# PCB_LTC6752.net
KiCad netlist of a schematic drawn in EAGLE
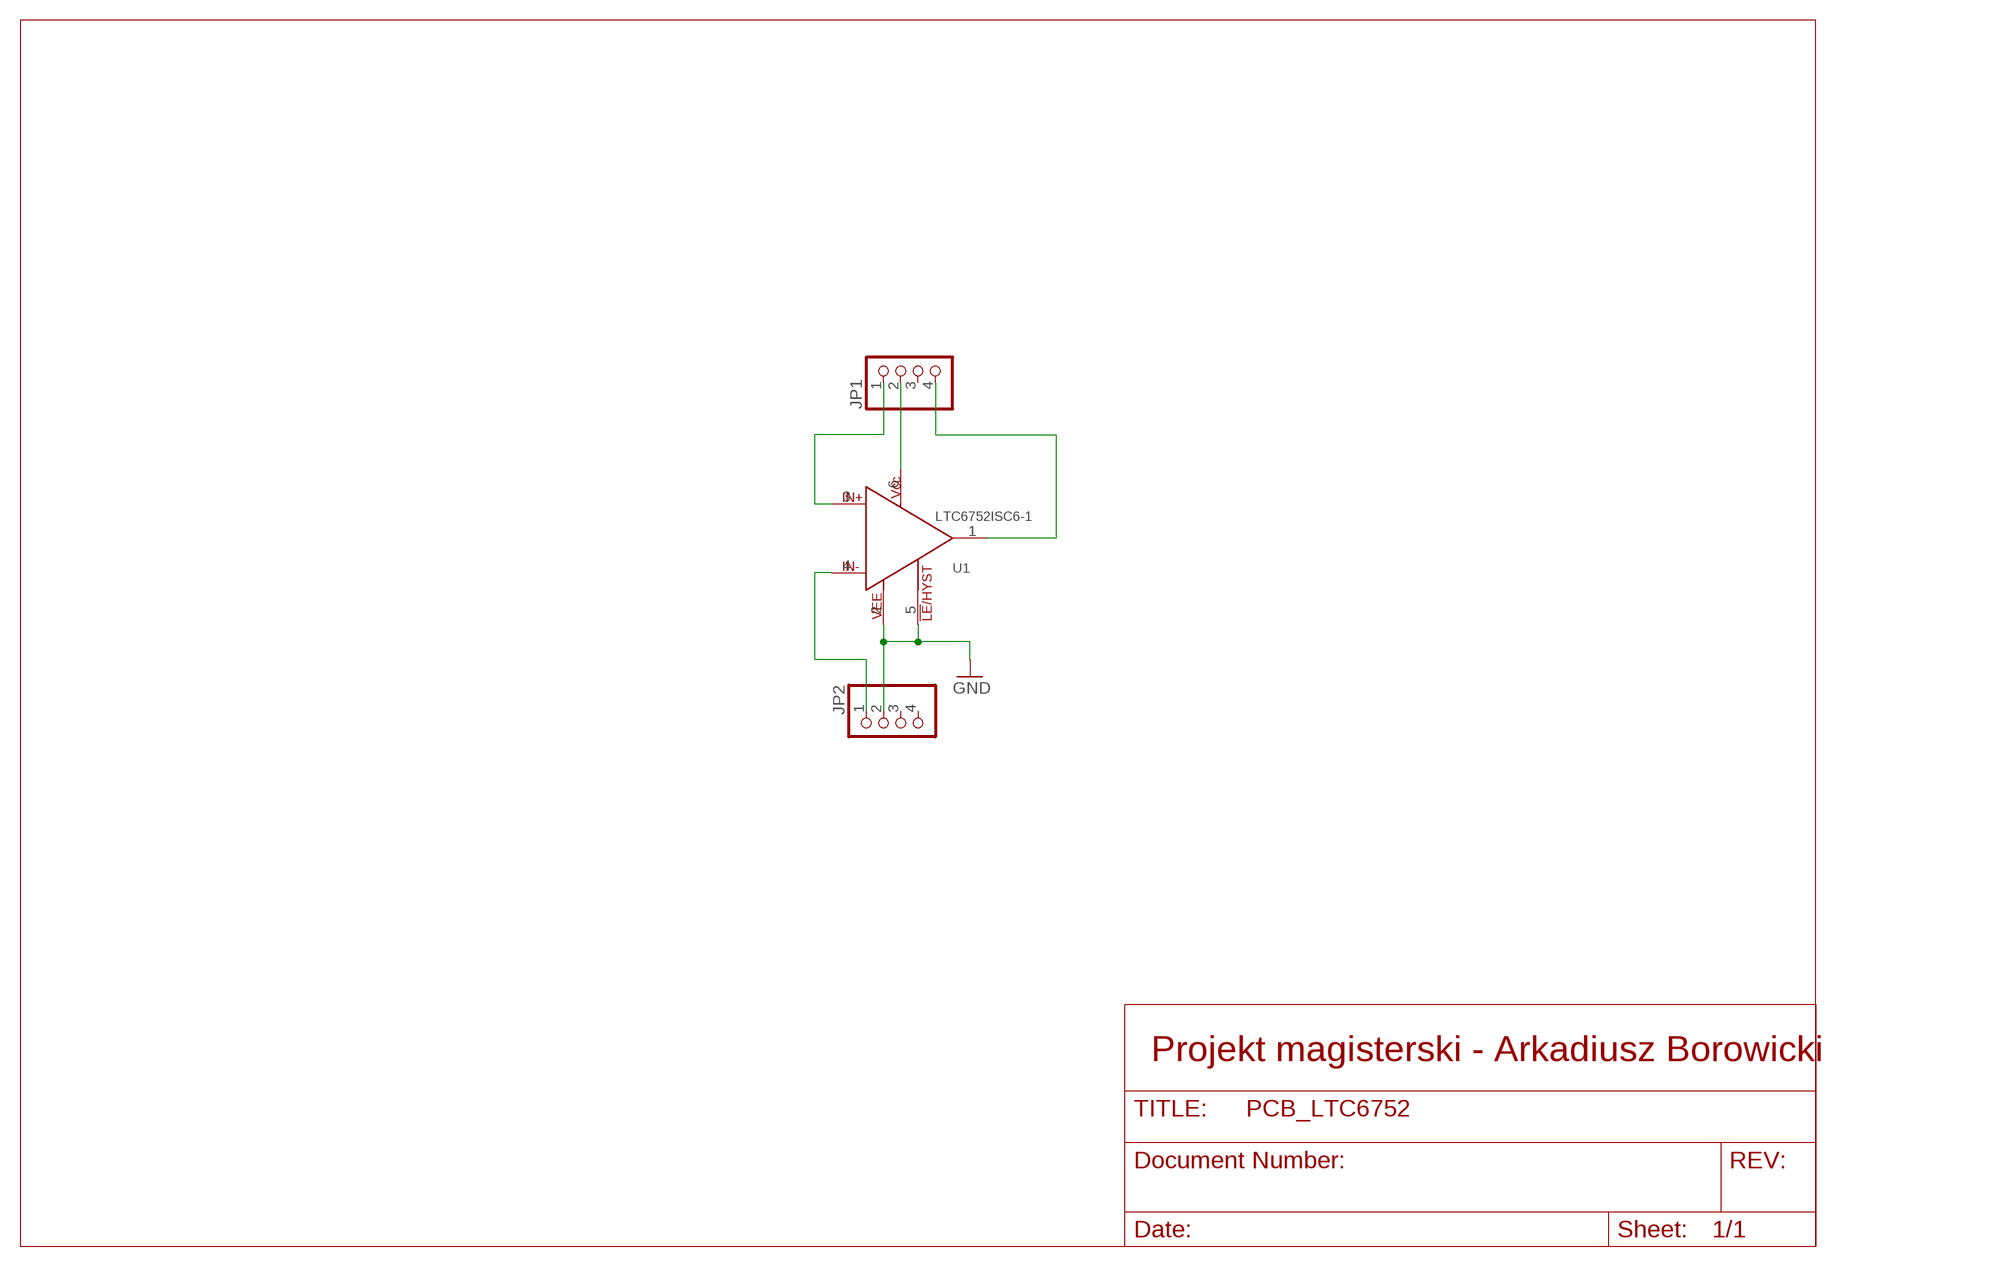
[diagram p0: schematic, sheet 1]

(export (version "E")
  (design (tool "Eeschema 10.0.6"))
  (components
    (comp (ref "JP1")
      (value "PINHD-1X4")
      (footprint "eagle-import:1X04")
      (libsource (lib "eagle-import") (part "PINHD-1X4"))
    )
    (comp (ref "JP2")
      (value "PINHD-1X4")
      (footprint "eagle-import:1X04")
      (libsource (lib "eagle-import") (part "PINHD-1X4"))
    )
    (comp (ref "U1")
      (value "LTC6752ISC6-1")
      (footprint "eagle-import:SC70-6")
      (fields (field (name "MF") "Analog Devices Inc."))
      (libsource (lib "eagle-import") (part "LTC6752ISC6-1"))
    )
  )
  (nets
    (net (code "1") (name "GND") (class "Default")
      (node (ref "JP2") (pin "2") (pinfunction "2_2") (pintype "passive"))
      (node (ref "U1") (pin "2") (pinfunction "VEE_2") (pintype "bidirectional"))
      (node (ref "U1") (pin "5") (pinfunction "HYST_5") (pintype "bidirectional"))
    )
    (net (code "2") (name "Net-(U1-IN+)") (class "Default")
      (node (ref "JP1") (pin "1") (pinfunction "1_1") (pintype "passive"))
      (node (ref "U1") (pin "3") (pinfunction "IN+_3") (pintype "bidirectional"))
    )
    (net (code "3") (name "Net-(U1-IN-)") (class "Default")
      (node (ref "JP2") (pin "1") (pinfunction "1_1") (pintype "passive"))
      (node (ref "U1") (pin "4") (pinfunction "IN-_4") (pintype "bidirectional"))
    )
    (net (code "4") (name "Net-(U1-OUT)") (class "Default")
      (node (ref "JP1") (pin "4") (pinfunction "4_4") (pintype "passive"))
      (node (ref "U1") (pin "1") (pinfunction "OUT_1") (pintype "bidirectional"))
    )
    (net (code "5") (name "Net-(U1-VCC)") (class "Default")
      (node (ref "JP1") (pin "2") (pinfunction "2_2") (pintype "passive"))
      (node (ref "U1") (pin "6") (pinfunction "VCC_6") (pintype "bidirectional"))
    )
    (net (code "6") (name "unconnected-(JP1-Pad3)") (class "Default")
      (node (ref "JP1") (pin "3") (pinfunction "3_3") (pintype "passive"))
    )
    (net (code "7") (name "unconnected-(JP2-Pad3)") (class "Default")
      (node (ref "JP2") (pin "3") (pinfunction "3_3") (pintype "passive"))
    )
    (net (code "8") (name "unconnected-(JP2-Pad4)") (class "Default")
      (node (ref "JP2") (pin "4") (pinfunction "4_4") (pintype "passive"))
    )
  )
)
